# Controller_Schematics.net
KiCad netlist of a schematic drawn in Altium Designer
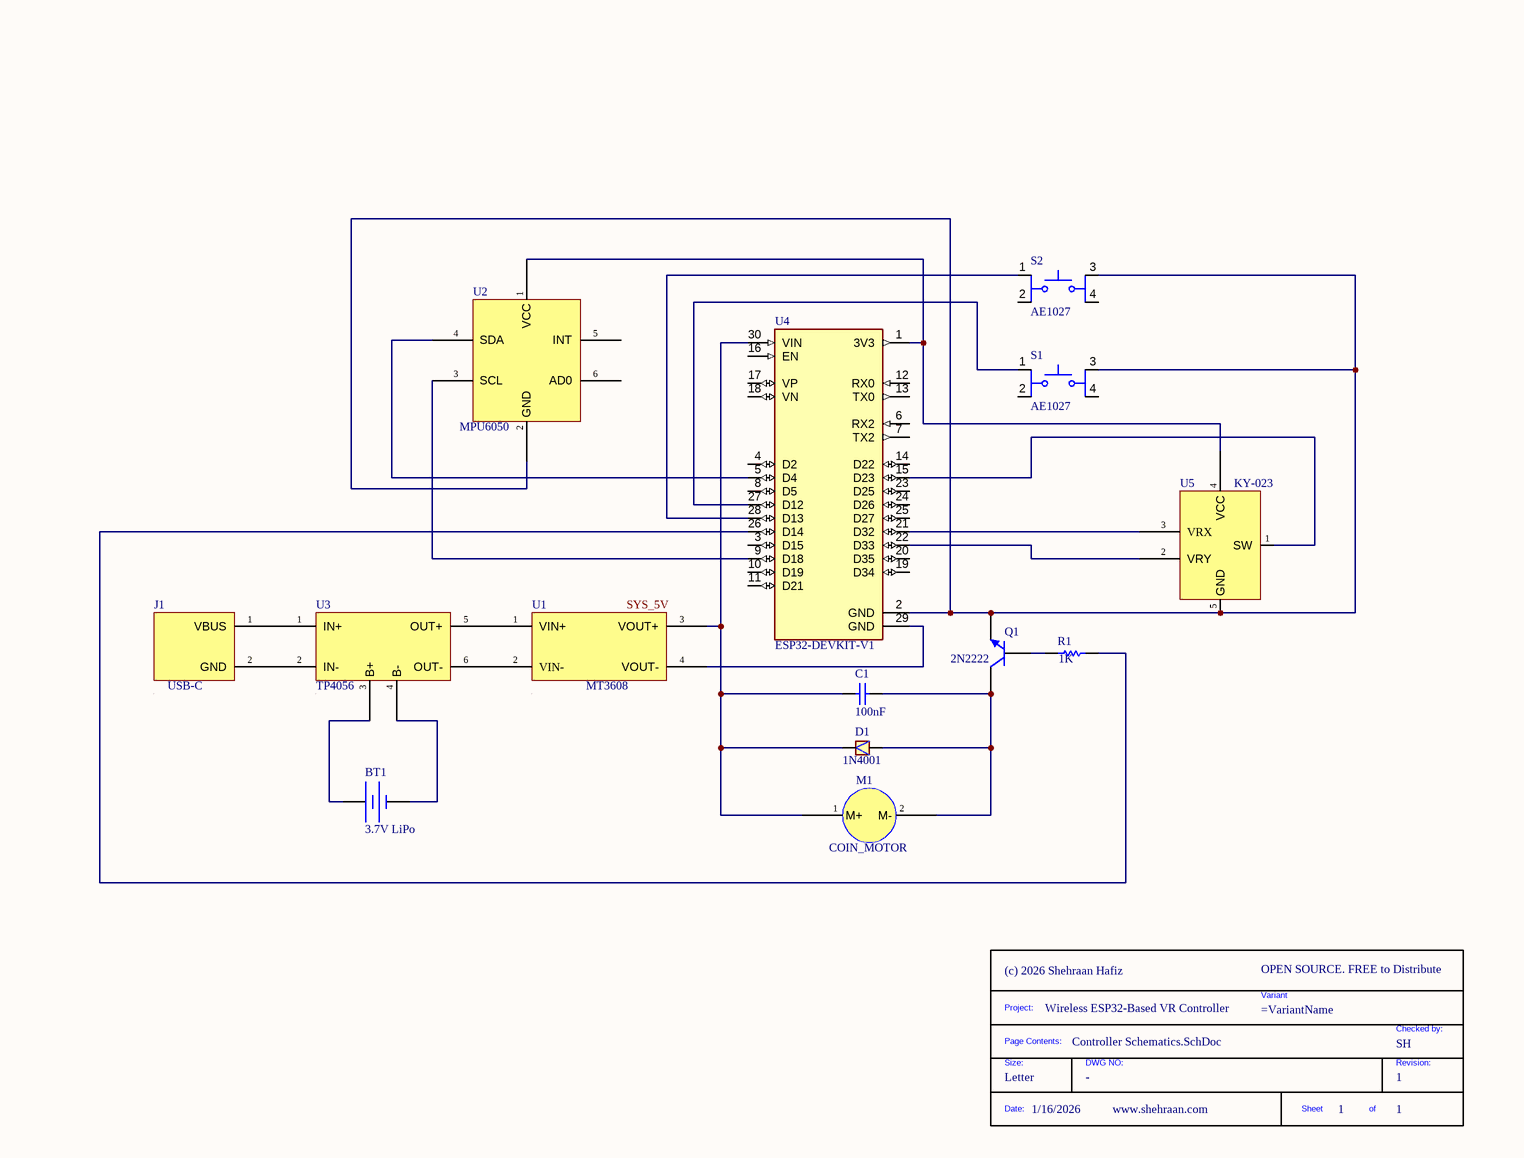
[diagram p0: Controller Schematics.SchDoc]

(export (version "E")
  (design (tool "Eeschema 10.0.6"))
  (components
    (comp (ref "*")
      (value "TITLE_BLOCK")
      (description "Standard Title Block")
      (fields (field (name "DWG NO") "-") (field (name "SIZE") "Letter") (field (name "CHECKED BY") "SH"))
      (libsource (lib "TITLE_BLOCK") (part "TITLE_BLOCK"))
    )
    (comp (ref "BT1")
      (value "Constant Voltage Source")
      (fields (field (name "103450 LIPO") "3.7V LiPo"))
      (libsource (lib "Simulation Generic Components") (part "Battery"))
    )
    (comp (ref "C1")
      (value "100nF")
      (description "Capacitor")
      (libsource (lib "Simulation Generic Components") (part "Capacitor"))
    )
    (comp (ref "D1")
      (value "1N4001")
      (footprint "DO41-10")
      (description "Diode Standard 50V 1A Through Hole DO-204AL (DO-41)")
      (fields (field (name "MF") "ON Semiconductor"))
      (libsource (lib "1N4001") (part "1N4001"))
    )
    (comp (ref "J1") (value "USB-C") (libsource (lib "USB_C_POWER") (part "USB-C")))
    (comp (ref "M1") (value "COIN_MOTOR") (libsource (lib "COIN_MOTOR") (part "COIN_MOTOR")))
    (comp (ref "Q1")
      (value "Bipolar NPN 3 Pins Transistor Modified Version of the Gummel-Poon Model")
      (libsource (lib "Simulation Generic Components") (part "BJT NPN_MGP"))
    )
    (comp (ref "R1")
      (value "1K")
      (description "Resistor")
      (libsource (lib "Simulation Generic Components") (part "Resistor"))
    )
    (comp (ref "S1")
      (value "AE1027")
      (footprint "SW_TL3305BF260QG")
      (description "Tactile Switch SPST-NO Top Actuated Surface Mount")
      (fields (field (name "MF") "E-Switch") (field (name "MP") "TL3305BF260QG"))
      (libsource (lib "TL3305BF260QG Pushbutton") (part "TL3305BF260QG"))
    )
    (comp (ref "S2")
      (value "AE1027")
      (footprint "SW_TL3305BF260QG")
      (description "Tactile Switch SPST-NO Top Actuated Surface Mount")
      (fields (field (name "MF") "E-Switch") (field (name "MP") "TL3305BF260QG"))
      (libsource (lib "TL3305BF260QG Pushbutton") (part "TL3305BF260QG"))
    )
    (comp (ref "U1") (value "MT3608") (libsource (lib "MT3608_MODULE") (part "MT3608")))
    (comp (ref "U2") (value "MPU6050") (libsource (lib "MPU6050_MODULE") (part "MPU6050")))
    (comp (ref "U3") (value "TP4056") (libsource (lib "TP4056_MODULE") (part "TP4056")))
    (comp (ref "U4")
      (value "ESP32-DEVKIT-V1")
      (footprint "MODULE_ESP32_DEVKIT_V1")
      (fields (field (name "MF") "Do it"))
      (libsource (lib "ESP32-DEVKIT-V1") (part "ESP32-DEVKIT-V1"))
    )
    (comp (ref "U5") (value "KY-023") (libsource (lib "JOYSTICK_MODULE") (part "KY-023")))
  )
  (nets
    (net (code "2") (name "Net-(D1-ANODE)") (class "Default")
      (node (ref "C1") (pin "2") (pinfunction "2_2") (pintype "passive"))
      (node (ref "D1") (pin "A") (pinfunction "ANODE_A") (pintype "passive"))
      (node (ref "M1") (pin "2") (pinfunction "M-_2") (pintype "passive"))
      (node (ref "Q1") (pin "1") (pinfunction "C_1") (pintype "passive"))
    )
    (net (code "3") (name "Net-(D1-CATHODE)") (class "Default")
      (node (ref "C1") (pin "1") (pinfunction "1_1") (pintype "passive"))
      (node (ref "D1") (pin "C") (pinfunction "CATHODE_C") (pintype "passive"))
      (node (ref "M1") (pin "1") (pinfunction "M+_1") (pintype "passive"))
      (node (ref "U1") (pin "3") (pinfunction "VOUT+_3") (pintype "passive"))
      (node (ref "U4") (pin "30") (pinfunction "VIN_30") (pintype "input"))
    )
    (net (code "4") (name "Net-(J1-GND)") (class "Default")
      (node (ref "J1") (pin "2") (pinfunction "GND_2") (pintype "passive"))
      (node (ref "U3") (pin "2") (pinfunction "IN-_2") (pintype "passive"))
    )
    (net (code "5") (name "Net-(J1-VBUS)") (class "Default")
      (node (ref "J1") (pin "1") (pinfunction "VBUS_1") (pintype "passive"))
      (node (ref "U3") (pin "1") (pinfunction "IN+_1") (pintype "passive"))
    )
    (net (code "6") (name "Net-(Q1-B)") (class "Default")
      (node (ref "Q1") (pin "2") (pinfunction "B_2") (pintype "passive"))
      (node (ref "R1") (pin "1") (pinfunction "1_1") (pintype "passive"))
    )
    (net (code "7") (name "Net-(Q1-E)") (class "Default")
      (node (ref "Q1") (pin "3") (pinfunction "E_3") (pintype "passive"))
      (node (ref "S1") (pin "3") (pinfunction "3_3") (pintype "passive"))
      (node (ref "S2") (pin "3") (pinfunction "3_3") (pintype "passive"))
      (node (ref "U2") (pin "2") (pinfunction "GND_2") (pintype "passive"))
      (node (ref "U4") (pin "2") (pinfunction "GND_2") (pintype "power_in"))
      (node (ref "U5") (pin "5") (pinfunction "GND_5") (pintype "passive"))
    )
    (net (code "8") (name "Net-(U1-VIN+)") (class "Default")
      (node (ref "U1") (pin "1") (pinfunction "VIN+_1") (pintype "passive"))
      (node (ref "U3") (pin "5") (pinfunction "OUT+_5") (pintype "passive"))
    )
    (net (code "9") (name "Net-(U1-VIN-)") (class "Default")
      (node (ref "U1") (pin "2") (pinfunction "VIN-_2") (pintype "passive"))
      (node (ref "U3") (pin "6") (pinfunction "OUT-_6") (pintype "passive"))
    )
    (net (code "10") (name "Net-(U1-VOUT-)") (class "Default")
      (node (ref "U1") (pin "4") (pinfunction "VOUT-_4") (pintype "passive"))
      (node (ref "U4") (pin "29") (pinfunction "GND_29") (pintype "power_in"))
    )
    (net (code "11") (name "Net-(U2-SCL)") (class "Default")
      (node (ref "U2") (pin "3") (pinfunction "SCL_3") (pintype "passive"))
      (node (ref "U4") (pin "9") (pinfunction "D18_9") (pintype "bidirectional"))
    )
    (net (code "12") (name "Net-(U2-SDA)") (class "Default")
      (node (ref "U2") (pin "4") (pinfunction "SDA_4") (pintype "passive"))
      (node (ref "U4") (pin "5") (pinfunction "D4_5") (pintype "bidirectional"))
    )
    (net (code "13") (name "Net-(U2-VCC)") (class "Default")
      (node (ref "U2") (pin "1") (pinfunction "VCC_1") (pintype "passive"))
      (node (ref "U4") (pin "1") (pinfunction "3V3_1") (pintype "output"))
      (node (ref "U5") (pin "4") (pinfunction "VCC_4") (pintype "passive"))
    )
    (net (code "14") (name "Net-(U3-B+)") (class "Default")
      (node (ref "BT1") (pin "1") (pinfunction "1_1") (pintype "passive"))
      (node (ref "U3") (pin "3") (pinfunction "B+_3") (pintype "passive"))
    )
    (net (code "15") (name "Net-(U3-B-)") (class "Default")
      (node (ref "BT1") (pin "2") (pinfunction "2_2") (pintype "passive"))
      (node (ref "U3") (pin "4") (pinfunction "B-_4") (pintype "passive"))
    )
    (net (code "16") (name "Net-(U4-D12)") (class "Default")
      (node (ref "S1") (pin "1") (pinfunction "1_1") (pintype "passive"))
      (node (ref "U4") (pin "27") (pinfunction "D12_27") (pintype "bidirectional"))
    )
    (net (code "17") (name "Net-(U4-D13)") (class "Default")
      (node (ref "S2") (pin "1") (pinfunction "1_1") (pintype "passive"))
      (node (ref "U4") (pin "28") (pinfunction "D13_28") (pintype "bidirectional"))
    )
    (net (code "18") (name "Net-(U4-D14)") (class "Default")
      (node (ref "R1") (pin "2") (pinfunction "2_2") (pintype "passive"))
      (node (ref "U4") (pin "26") (pinfunction "D14_26") (pintype "bidirectional"))
    )
    (net (code "19") (name "Net-(U4-D23)") (class "Default")
      (node (ref "U4") (pin "15") (pinfunction "D23_15") (pintype "bidirectional"))
      (node (ref "U5") (pin "1") (pinfunction "SW_1") (pintype "passive"))
    )
    (net (code "20") (name "Net-(U4-D32)") (class "Default")
      (node (ref "U4") (pin "21") (pinfunction "D32_21") (pintype "bidirectional"))
      (node (ref "U5") (pin "3") (pinfunction "VRX_3") (pintype "passive"))
    )
    (net (code "21") (name "Net-(U4-D33)") (class "Default")
      (node (ref "U4") (pin "22") (pinfunction "D33_22") (pintype "bidirectional"))
      (node (ref "U5") (pin "2") (pinfunction "VRY_2") (pintype "passive"))
    )
    (net (code "22") (name "unconnected-(S1-Pad2)") (class "Default")
      (node (ref "S1") (pin "2") (pinfunction "2_2") (pintype "passive"))
    )
    (net (code "23") (name "unconnected-(S1-Pad4)") (class "Default")
      (node (ref "S1") (pin "4") (pinfunction "4_4") (pintype "passive"))
    )
    (net (code "24") (name "unconnected-(S2-Pad2)") (class "Default")
      (node (ref "S2") (pin "2") (pinfunction "2_2") (pintype "passive"))
    )
    (net (code "25") (name "unconnected-(S2-Pad4)") (class "Default")
      (node (ref "S2") (pin "4") (pinfunction "4_4") (pintype "passive"))
    )
    (net (code "26") (name "unconnected-(U2-AD0-Pad6)") (class "Default")
      (node (ref "U2") (pin "6") (pinfunction "AD0_6") (pintype "passive"))
    )
    (net (code "27") (name "unconnected-(U2-INT-Pad5)") (class "Default")
      (node (ref "U2") (pin "5") (pinfunction "INT_5") (pintype "passive"))
    )
    (net (code "28") (name "unconnected-(U4-D2-Pad4)") (class "Default")
      (node (ref "U4") (pin "4") (pinfunction "D2_4") (pintype "bidirectional"))
    )
    (net (code "29") (name "unconnected-(U4-D5-Pad8)") (class "Default")
      (node (ref "U4") (pin "8") (pinfunction "D5_8") (pintype "bidirectional"))
    )
    (net (code "30") (name "unconnected-(U4-D15-Pad3)") (class "Default")
      (node (ref "U4") (pin "3") (pinfunction "D15_3") (pintype "bidirectional"))
    )
    (net (code "31") (name "unconnected-(U4-D19-Pad10)") (class "Default")
      (node (ref "U4") (pin "10") (pinfunction "D19_10") (pintype "bidirectional"))
    )
    (net (code "32") (name "unconnected-(U4-D21-Pad11)") (class "Default")
      (node (ref "U4") (pin "11") (pinfunction "D21_11") (pintype "bidirectional"))
    )
    (net (code "33") (name "unconnected-(U4-D22-Pad14)") (class "Default")
      (node (ref "U4") (pin "14") (pinfunction "D22_14") (pintype "bidirectional"))
    )
    (net (code "34") (name "unconnected-(U4-D25-Pad23)") (class "Default")
      (node (ref "U4") (pin "23") (pinfunction "D25_23") (pintype "bidirectional"))
    )
    (net (code "35") (name "unconnected-(U4-D26-Pad24)") (class "Default")
      (node (ref "U4") (pin "24") (pinfunction "D26_24") (pintype "bidirectional"))
    )
    (net (code "36") (name "unconnected-(U4-D27-Pad25)") (class "Default")
      (node (ref "U4") (pin "25") (pinfunction "D27_25") (pintype "bidirectional"))
    )
    (net (code "37") (name "unconnected-(U4-D34-Pad19)") (class "Default")
      (node (ref "U4") (pin "19") (pinfunction "D34_19") (pintype "bidirectional"))
    )
    (net (code "38") (name "unconnected-(U4-D35-Pad20)") (class "Default")
      (node (ref "U4") (pin "20") (pinfunction "D35_20") (pintype "bidirectional"))
    )
    (net (code "39") (name "unconnected-(U4-EN-Pad16)") (class "Default")
      (node (ref "U4") (pin "16") (pinfunction "EN_16") (pintype "input"))
    )
    (net (code "40") (name "unconnected-(U4-RX0-Pad12)") (class "Default")
      (node (ref "U4") (pin "12") (pinfunction "RX0_12") (pintype "input"))
    )
    (net (code "41") (name "unconnected-(U4-RX2-Pad6)") (class "Default")
      (node (ref "U4") (pin "6") (pinfunction "RX2_6") (pintype "input"))
    )
    (net (code "42") (name "unconnected-(U4-TX0-Pad13)") (class "Default")
      (node (ref "U4") (pin "13") (pinfunction "TX0_13") (pintype "output"))
    )
    (net (code "43") (name "unconnected-(U4-TX2-Pad7)") (class "Default")
      (node (ref "U4") (pin "7") (pinfunction "TX2_7") (pintype "output"))
    )
    (net (code "44") (name "unconnected-(U4-VN-Pad18)") (class "Default")
      (node (ref "U4") (pin "18") (pinfunction "VN_18") (pintype "bidirectional"))
    )
    (net (code "45") (name "unconnected-(U4-VP-Pad17)") (class "Default")
      (node (ref "U4") (pin "17") (pinfunction "VP_17") (pintype "bidirectional"))
    )
  )
)
